# ESP32.net
KiCad netlist of a schematic drawn in Altium Designer
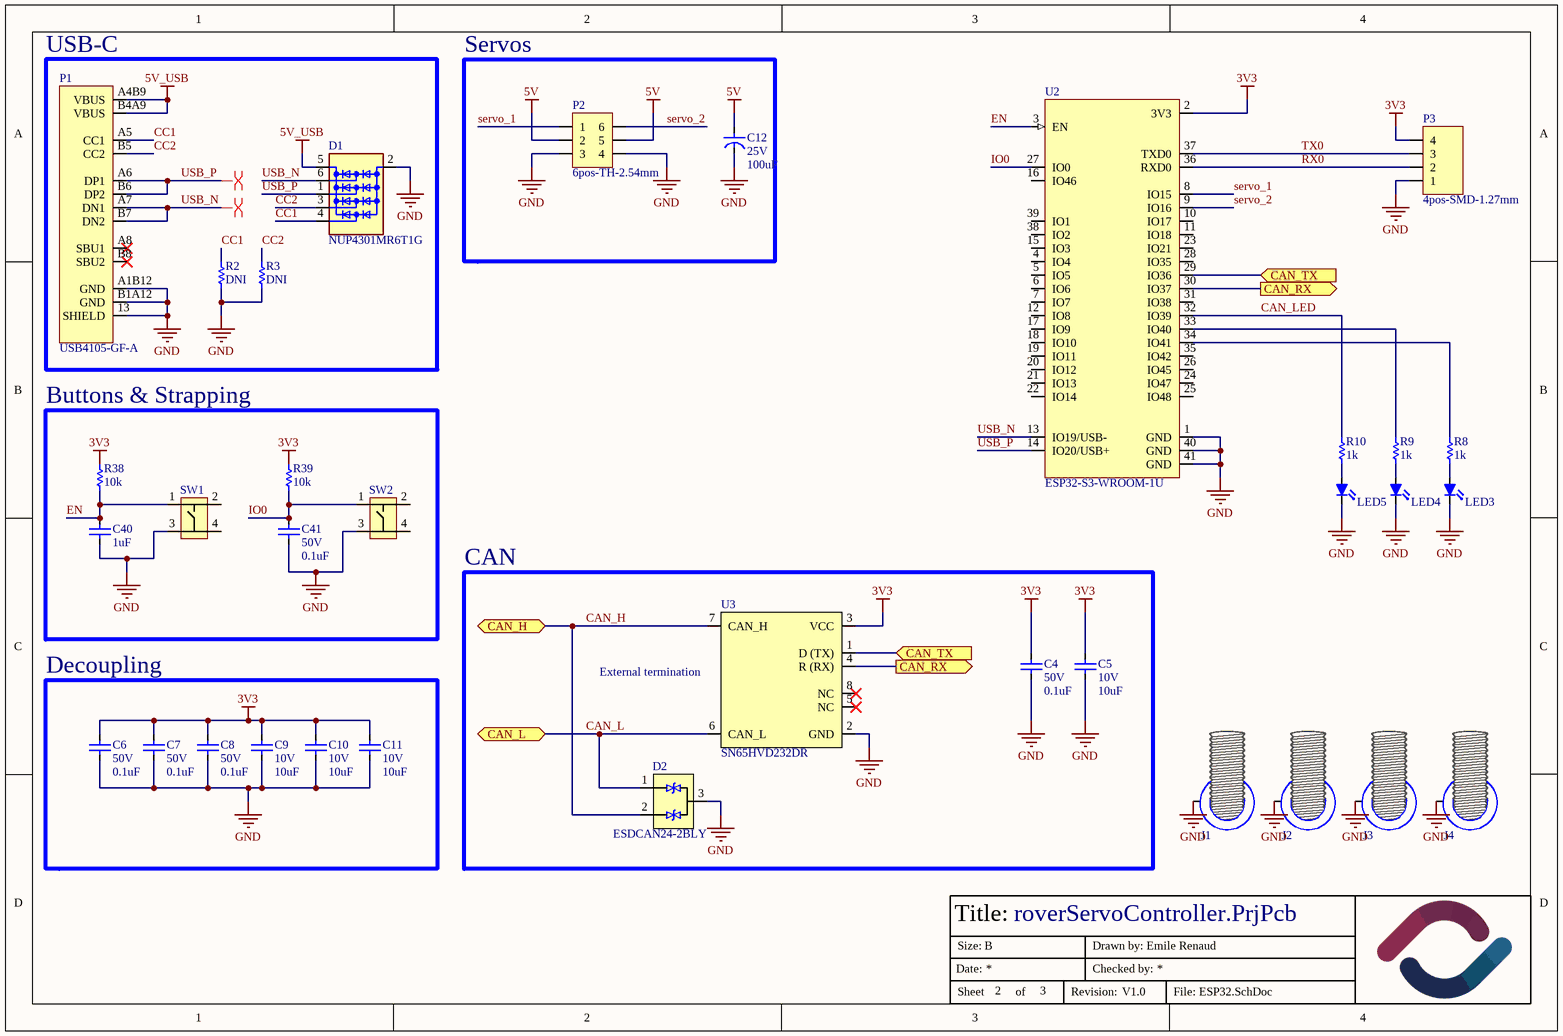
[diagram p0: ESP32.SchDoc]

(export (version "E")
  (design (tool "Eeschema 10.0.6"))
  (components
    (comp (ref "C4")
      (value "0.1uF")
      (footprint "CAPACITOR-0603")
      (description "Capacitor-0603-0.1uF-50V-X7R")
      (fields (field (name "VOLT") "50V"))
      (libsource (lib "Capacitors") (part "Capacitor-0603-0.1uF-50V-X7R"))
    )
    (comp (ref "C5")
      (value "10uF")
      (footprint "CAPACITOR-0603")
      (description "10 µF ±20% 10V Ceramic Capacitor X5R 0603 (1608 Metric)")
      (fields (field (name "VOLT") "10V") (field (name "Comment") "Capacitor-0603-10uF-10V-X5R"))
      (libsource (lib "Capacitors") (part "Capacitor-0603-10uF-10V-X5R"))
    )
    (comp (ref "C6")
      (value "0.1uF")
      (footprint "CAPACITOR-0603")
      (description "Capacitor-0603-0.1uF-50V-X7R")
      (fields (field (name "VOLT") "50V"))
      (libsource (lib "Capacitors") (part "Capacitor-0603-0.1uF-50V-X7R"))
    )
    (comp (ref "C7")
      (value "0.1uF")
      (footprint "CAPACITOR-0603")
      (description "Capacitor-0603-0.1uF-50V-X7R")
      (fields (field (name "VOLT") "50V"))
      (libsource (lib "Capacitors") (part "Capacitor-0603-0.1uF-50V-X7R"))
    )
    (comp (ref "C8")
      (value "0.1uF")
      (footprint "CAPACITOR-0603")
      (description "Capacitor-0603-0.1uF-50V-X7R")
      (fields (field (name "VOLT") "50V"))
      (libsource (lib "Capacitors") (part "Capacitor-0603-0.1uF-50V-X7R"))
    )
    (comp (ref "C9")
      (value "10uF")
      (footprint "CAPACITOR-0603")
      (description "10 µF ±20% 10V Ceramic Capacitor X5R 0603 (1608 Metric)")
      (fields (field (name "VOLT") "10V") (field (name "Comment") "Capacitor-0603-10uF-10V-X5R"))
      (libsource (lib "Capacitors") (part "Capacitor-0603-10uF-10V-X5R"))
    )
    (comp (ref "C10")
      (value "10uF")
      (footprint "CAPACITOR-0603")
      (description "10 µF ±20% 10V Ceramic Capacitor X5R 0603 (1608 Metric)")
      (fields (field (name "VOLT") "10V") (field (name "Comment") "Capacitor-0603-10uF-10V-X5R"))
      (libsource (lib "Capacitors") (part "Capacitor-0603-10uF-10V-X5R"))
    )
    (comp (ref "C11")
      (value "10uF")
      (footprint "CAPACITOR-0603")
      (description "10 µF ±20% 10V Ceramic Capacitor X5R 0603 (1608 Metric)")
      (fields (field (name "VOLT") "10V") (field (name "Comment") "Capacitor-0603-10uF-10V-X5R"))
      (libsource (lib "Capacitors") (part "Capacitor-0603-10uF-10V-X5R"))
    )
    (comp (ref "C12")
      (value "100uF")
      (footprint "CAPACITOR-Aluminium-5x11mm-2mmPitch - SIDE")
      (description "CAP ALUM 100UF 20% 25V RADIAL")
      (fields (field (name "VOLT") "25V") (field (name "Comment") "CAP ALUM 100UF 20% 25V RADIAL SIDE"))
      (libsource (lib "Capacitors-Electrolytic") (part "Capacitor-100uF-25V-Side"))
    )
    (comp (ref "C40")
      (value "1uF")
      (footprint "CAPACITOR-0603")
      (description "Capacitor-0603-1uF-25V-X5R")
      (libsource (lib "Capacitors") (part "Capacitor-0603-1uF-25V-X5R"))
    )
    (comp (ref "C41")
      (value "0.1uF")
      (footprint "CAPACITOR-0603")
      (description "Capacitor-0603-0.1uF-50V-X7R")
      (fields (field (name "VOLT") "50V"))
      (libsource (lib "Capacitors") (part "Capacitor-0603-0.1uF-50V-X7R"))
    )
    (comp (ref "D1")
      (value "NUP4301MR6T1G")
      (footprint "SOT-23-6")
      (description "4CH Clamp Ipp Tvs Diode Surface Mount SOT23-6 (SC74)")
      (libsource (lib "diodes") (part "NUP4301MR6T1G"))
    )
    (comp (ref "D2")
      (value "ESDCAN24-2BLY")
      (footprint "SOT-23-3")
      (description "55V Clamp 6A (8/20µs) Ipp Tvs Diode Surface Mount SOT-23")
      (libsource (lib "diodes-tvs") (part "ESDCAN24-2BLY"))
    )
    (comp (ref "J1")
      (value "hole")
      (footprint "HOLE-3.40MM-M3-8MMEYELET")
      (description "Hole for M3 Bolt with 8mm pad")
      (libsource (lib "JumpersAndHoles") (part "Hole 3.40mm M3-Eyelet"))
    )
    (comp (ref "J2")
      (value "hole")
      (footprint "HOLE-3.40MM-M3-8MMEYELET")
      (description "Hole for M3 Bolt with 8mm pad")
      (libsource (lib "JumpersAndHoles") (part "Hole 3.40mm M3-Eyelet"))
    )
    (comp (ref "J3")
      (value "hole")
      (footprint "HOLE-3.40MM-M3-8MMEYELET")
      (description "Hole for M3 Bolt with 8mm pad")
      (libsource (lib "JumpersAndHoles") (part "Hole 3.40mm M3-Eyelet"))
    )
    (comp (ref "J4")
      (value "hole")
      (footprint "HOLE-3.40MM-M3-8MMEYELET")
      (description "Hole for M3 Bolt with 8mm pad")
      (libsource (lib "JumpersAndHoles") (part "Hole 3.40mm M3-Eyelet"))
    )
    (comp (ref "LED3")
      (value "3147-B1931NB--20C007614U1930CT-ND")
      (footprint "LED-0603-2PIN-SILKSCREEN")
      (description "LED BLUE CLEAR 0603 SMD")
      (libsource (lib "LEDs") (part "LED_BLUE"))
    )
    (comp (ref "LED4")
      (value "3147-B1931NB--20C007614U1930CT-ND")
      (footprint "LED-0603-2PIN-SILKSCREEN")
      (description "LED BLUE CLEAR 0603 SMD")
      (libsource (lib "LEDs") (part "LED_BLUE"))
    )
    (comp (ref "LED5")
      (value "3147-B1931NB--20C007614U1930CT-ND")
      (footprint "LED-0603-2PIN-SILKSCREEN")
      (description "LED BLUE CLEAR 0603 SMD")
      (libsource (lib "LEDs") (part "LED_BLUE"))
    )
    (comp (ref "P1")
      (value "USB4105-GF-A")
      (footprint "USB-C")
      (description "CONN RCP USB2.0 TYP C 24P SMD RA\r\n5A")
      (libsource (lib "PC-connector") (part "USB4105-GF-A"))
    )
    (comp (ref "P2")
      (value "6pos-TH-2.54mm")
      (footprint "HDR2X3")
      (description "6pos TH 2.54mm Header")
      (libsource (lib "Header") (part "6pos-TH-2.54mm 2x3"))
    )
    (comp (ref "P3")
      (value "4pos-SMD-1.27mm")
      (footprint "HDR1X4-SMD-50mils")
      (description "4pos SMD 1.27mm")
      (libsource (lib "Header") (part "4pos-SMD-1.27mm"))
    )
    (comp (ref "R2")
      (value "DNI")
      (footprint "RESISTOR-0603")
      (description "0603 footprint DO NOT INSTALL")
      (fields (field (name "Comment") "Resistor-0603-5.1k"))
      (libsource (lib "Resistors") (part "Resistor-0603-DNI"))
    )
    (comp (ref "R3")
      (value "DNI")
      (footprint "RESISTOR-0603")
      (description "0603 footprint DO NOT INSTALL")
      (fields (field (name "Comment") "Resistor-0603-5.1k"))
      (libsource (lib "Resistors") (part "Resistor-0603-DNI"))
    )
    (comp (ref "R8")
      (value "1k")
      (footprint "Resistor-0603")
      (description "Resistor0603-1k")
      (fields (field (name "Comment") "SMT resistor"))
      (libsource (lib "Resistors") (part "Resistor-0603-1k"))
    )
    (comp (ref "R9")
      (value "1k")
      (footprint "Resistor-0603")
      (description "Resistor0603-1k")
      (fields (field (name "Comment") "SMT resistor"))
      (libsource (lib "Resistors") (part "Resistor-0603-1k"))
    )
    (comp (ref "R10")
      (value "1k")
      (footprint "Resistor-0603")
      (description "Resistor0603-1k")
      (fields (field (name "Comment") "SMT resistor"))
      (libsource (lib "Resistors") (part "Resistor-0603-1k"))
    )
    (comp (ref "R38")
      (value "10k")
      (footprint "Resistor-0603")
      (description "Resistor0603-10k")
      (fields (field (name "Comment") "SMT resistor"))
      (libsource (lib "Resistors") (part "Resistor0603-10k"))
    )
    (comp (ref "R39")
      (value "10k")
      (footprint "Resistor-0603")
      (description "Resistor0603-10k")
      (fields (field (name "Comment") "SMT resistor"))
      (libsource (lib "Resistors") (part "Resistor0603-10k"))
    )
    (comp (ref "SW1")
      (value "PTS815 SJM 250 SMTR LFS")
      (footprint "SW4_PTS815 SJM 250 SMTR LFS_CNK")
      (description "TACT 4.2 X 3.2, 2.5 MM H, 180GF,")
      (libsource (lib "THTPushButtonSwitches") (part "PTS815 SJM 250 SMTR LFS"))
    )
    (comp (ref "SW2")
      (value "PTS815 SJM 250 SMTR LFS")
      (footprint "SW4_PTS815 SJM 250 SMTR LFS_CNK")
      (description "TACT 4.2 X 3.2, 2.5 MM H, 180GF,")
      (libsource (lib "THTPushButtonSwitches") (part "PTS815 SJM 250 SMTR LFS"))
    )
    (comp (ref "U2")
      (value "ESP32-S3-WROOM-1U")
      (footprint "ESP32-S3-WROOM-1U")
      (description "2.4 GHz Wi-Fi (802.11 b/g/n) and Bluetooth 5 (LE) module")
      (fields (field (name "MF") "Espressif Systems"))
      (libsource (lib "Microcontrollers") (part "ESP32-S3-WROOM-1U"))
    )
    (comp (ref "U3")
      (value "SN65HVD232DR")
      (footprint "SOIC-8")
      (description "1/1 Transceiver Half CANbus 8-SOIC")
      (libsource (lib "Transceiver") (part "SN65HVD232DR"))
    )
  )
  (nets
    (net (code "1") (name "/CAN_H") (class "Default")
      (node (ref "D2") (pin "2") (pinfunction "GND_2") (pintype "passive"))
      (node (ref "U3") (pin "7") (pinfunction "CAN_H_7") (pintype "passive"))
    )
    (net (code "2") (name "/CAN_L") (class "Default")
      (node (ref "D2") (pin "1") (pinfunction "L2_1") (pintype "passive"))
      (node (ref "U3") (pin "6") (pinfunction "CAN_L_6") (pintype "passive"))
    )
    (net (code "3") (name "/CAN_LED") (class "Default")
      (node (ref "R10") (pin "2") (pinfunction "2_2") (pintype "passive"))
      (node (ref "U2") (pin "32") (pinfunction "IO39_32") (pintype "bidirectional"))
    )
    (net (code "4") (name "/CAN_RX") (class "Default")
      (node (ref "U2") (pin "30") (pinfunction "IO37_30") (pintype "bidirectional"))
      (node (ref "U3") (pin "4") (pinfunction "R_(RX)_4") (pintype "passive"))
    )
    (net (code "5") (name "/CAN_TX") (class "Default")
      (node (ref "U2") (pin "29") (pinfunction "IO36_29") (pintype "bidirectional"))
      (node (ref "U3") (pin "1") (pinfunction "D_(TX)_1") (pintype "passive"))
    )
    (net (code "6") (name "/CC1") (class "Default")
      (node (ref "D1") (pin "4") (pinfunction "L4_4") (pintype "passive"))
      (node (ref "P1") (pin "A5") (pinfunction "CC1_A5") (pintype "passive"))
      (node (ref "R2") (pin "2") (pinfunction "2_2") (pintype "passive"))
    )
    (net (code "7") (name "/CC2") (class "Default")
      (node (ref "D1") (pin "3") (pinfunction "L3_3") (pintype "passive"))
      (node (ref "P1") (pin "B5") (pinfunction "CC2_B5") (pintype "passive"))
      (node (ref "R3") (pin "2") (pinfunction "2_2") (pintype "passive"))
    )
    (net (code "8") (name "/EN") (class "Default")
      (node (ref "C40") (pin "2") (pinfunction "2_2") (pintype "passive"))
      (node (ref "R38") (pin "1") (pinfunction "1_1") (pintype "passive"))
      (node (ref "SW1") (pin "1") (pinfunction "1_1") (pintype "passive"))
      (node (ref "U2") (pin "3") (pinfunction "EN_3") (pintype "input"))
    )
    (net (code "9") (name "/IO0") (class "Default")
      (node (ref "C41") (pin "2") (pinfunction "2_2") (pintype "passive"))
      (node (ref "R39") (pin "1") (pinfunction "1_1") (pintype "passive"))
      (node (ref "SW2") (pin "1") (pinfunction "1_1") (pintype "passive"))
      (node (ref "U2") (pin "27") (pinfunction "IO0_27") (pintype "bidirectional"))
    )
    (net (code "10") (name "/RX0") (class "Default")
      (node (ref "P3") (pin "2") (pinfunction "2_2") (pintype "passive"))
      (node (ref "U2") (pin "36") (pinfunction "RXD0_36") (pintype "bidirectional"))
    )
    (net (code "11") (name "/TX0") (class "Default")
      (node (ref "P3") (pin "3") (pinfunction "3_3") (pintype "passive"))
      (node (ref "U2") (pin "37") (pinfunction "TXD0_37") (pintype "bidirectional"))
    )
    (net (code "12") (name "/USB_N") (class "Default")
      (node (ref "D1") (pin "6") (pinfunction "L1_6") (pintype "passive"))
      (node (ref "P1") (pin "A7") (pinfunction "DN1_A7") (pintype "passive"))
      (node (ref "P1") (pin "B7") (pinfunction "DN2_B7") (pintype "passive"))
      (node (ref "U2") (pin "13") (pinfunction "IO19/USB-_13") (pintype "bidirectional"))
    )
    (net (code "13") (name "/USB_P") (class "Default")
      (node (ref "D1") (pin "1") (pinfunction "L2_1") (pintype "passive"))
      (node (ref "P1") (pin "A6") (pinfunction "DP1_A6") (pintype "passive"))
      (node (ref "P1") (pin "B6") (pinfunction "DP2_B6") (pintype "passive"))
      (node (ref "U2") (pin "14") (pinfunction "IO20/USB+_14") (pintype "bidirectional"))
    )
    (net (code "14") (name "/servo_1") (class "Default")
      (node (ref "P2") (pin "1") (pinfunction "1_1") (pintype "passive"))
      (node (ref "U2") (pin "8") (pinfunction "IO15_8") (pintype "bidirectional"))
    )
    (net (code "15") (name "/servo_2") (class "Default")
      (node (ref "P2") (pin "6") (pinfunction "6_6") (pintype "passive"))
      (node (ref "U2") (pin "9") (pinfunction "IO16_9") (pintype "bidirectional"))
    )
    (net (code "16") (name "3V3") (class "Default")
      (node (ref "C10") (pin "2") (pinfunction "2_2") (pintype "passive"))
      (node (ref "C11") (pin "2") (pinfunction "2_2") (pintype "passive"))
      (node (ref "C4") (pin "2") (pinfunction "2_2") (pintype "passive"))
      (node (ref "C5") (pin "2") (pinfunction "2_2") (pintype "passive"))
      (node (ref "C6") (pin "2") (pinfunction "2_2") (pintype "passive"))
      (node (ref "C7") (pin "2") (pinfunction "2_2") (pintype "passive"))
      (node (ref "C8") (pin "2") (pinfunction "2_2") (pintype "passive"))
      (node (ref "C9") (pin "2") (pinfunction "2_2") (pintype "passive"))
      (node (ref "P3") (pin "4") (pinfunction "4_4") (pintype "passive"))
      (node (ref "R38") (pin "2") (pinfunction "2_2") (pintype "passive"))
      (node (ref "R39") (pin "2") (pinfunction "2_2") (pintype "passive"))
      (node (ref "U2") (pin "2") (pinfunction "3V3_2") (pintype "power_in"))
      (node (ref "U3") (pin "3") (pinfunction "VCC_3") (pintype "passive"))
    )
    (net (code "17") (name "5V") (class "Default")
      (node (ref "C12") (pin "1") (pinfunction "1_1") (pintype "passive"))
      (node (ref "P2") (pin "2") (pinfunction "2_2") (pintype "passive"))
      (node (ref "P2") (pin "5") (pinfunction "5_5") (pintype "passive"))
    )
    (net (code "18") (name "5V_USB") (class "Default")
      (node (ref "D1") (pin "5") (pinfunction "VDD_5") (pintype "passive"))
      (node (ref "P1") (pin "A4B9") (pinfunction "VBUS_A4B9") (pintype "passive"))
      (node (ref "P1") (pin "B4A9") (pinfunction "VBUS_B4A9") (pintype "passive"))
    )
    (net (code "19") (name "GND") (class "Default")
      (node (ref "C10") (pin "1") (pinfunction "1_1") (pintype "passive"))
      (node (ref "C11") (pin "1") (pinfunction "1_1") (pintype "passive"))
      (node (ref "C12") (pin "2") (pinfunction "2_2") (pintype "passive"))
      (node (ref "C4") (pin "1") (pinfunction "1_1") (pintype "passive"))
      (node (ref "C40") (pin "1") (pinfunction "1_1") (pintype "passive"))
      (node (ref "C41") (pin "1") (pinfunction "1_1") (pintype "passive"))
      (node (ref "C5") (pin "1") (pinfunction "1_1") (pintype "passive"))
      (node (ref "C6") (pin "1") (pinfunction "1_1") (pintype "passive"))
      (node (ref "C7") (pin "1") (pinfunction "1_1") (pintype "passive"))
      (node (ref "C8") (pin "1") (pinfunction "1_1") (pintype "passive"))
      (node (ref "C9") (pin "1") (pinfunction "1_1") (pintype "passive"))
      (node (ref "D1") (pin "2") (pinfunction "GND_2") (pintype "passive"))
      (node (ref "D2") (pin "3") (pinfunction "L3_3") (pintype "passive"))
      (node (ref "J1") (pin "1") (pinfunction "1_1") (pintype "passive"))
      (node (ref "J2") (pin "1") (pinfunction "1_1") (pintype "passive"))
      (node (ref "J3") (pin "1") (pinfunction "1_1") (pintype "passive"))
      (node (ref "J4") (pin "1") (pinfunction "1_1") (pintype "passive"))
      (node (ref "LED3") (pin "1") (pinfunction "K_1") (pintype "passive"))
      (node (ref "LED4") (pin "1") (pinfunction "K_1") (pintype "passive"))
      (node (ref "LED5") (pin "1") (pinfunction "K_1") (pintype "passive"))
      (node (ref "P1") (pin "13") (pinfunction "SHIELD_13") (pintype "passive"))
      (node (ref "P1") (pin "A1B12") (pinfunction "GND_A1B12") (pintype "passive"))
      (node (ref "P1") (pin "B1A12") (pinfunction "GND_B1A12") (pintype "passive"))
      (node (ref "P2") (pin "3") (pinfunction "3_3") (pintype "passive"))
      (node (ref "P2") (pin "4") (pinfunction "4_4") (pintype "passive"))
      (node (ref "P3") (pin "1") (pinfunction "1_1") (pintype "passive"))
      (node (ref "R2") (pin "1") (pinfunction "1_1") (pintype "passive"))
      (node (ref "R3") (pin "1") (pinfunction "1_1") (pintype "passive"))
      (node (ref "SW1") (pin "3") (pinfunction "3_3") (pintype "passive"))
      (node (ref "SW2") (pin "3") (pinfunction "3_3") (pintype "passive"))
      (node (ref "U2") (pin "1") (pinfunction "GND_1") (pintype "power_in"))
      (node (ref "U2") (pin "40") (pinfunction "GND_40") (pintype "power_in"))
      (node (ref "U2") (pin "41") (pinfunction "GND_41") (pintype "power_in"))
      (node (ref "U3") (pin "2") (pinfunction "GND_2") (pintype "passive"))
    )
    (net (code "20") (name "Net-(LED3-R)") (class "Default")
      (node (ref "LED3") (pin "2") (pinfunction "R_2") (pintype "passive"))
      (node (ref "R8") (pin "1") (pinfunction "1_1") (pintype "passive"))
    )
    (net (code "21") (name "Net-(LED4-R)") (class "Default")
      (node (ref "LED4") (pin "2") (pinfunction "R_2") (pintype "passive"))
      (node (ref "R9") (pin "1") (pinfunction "1_1") (pintype "passive"))
    )
    (net (code "22") (name "Net-(LED5-R)") (class "Default")
      (node (ref "LED5") (pin "2") (pinfunction "R_2") (pintype "passive"))
      (node (ref "R10") (pin "1") (pinfunction "1_1") (pintype "passive"))
    )
    (net (code "23") (name "Net-(U2-IO40)") (class "Default")
      (node (ref "R9") (pin "2") (pinfunction "2_2") (pintype "passive"))
      (node (ref "U2") (pin "33") (pinfunction "IO40_33") (pintype "bidirectional"))
    )
    (net (code "24") (name "Net-(U2-IO41)") (class "Default")
      (node (ref "R8") (pin "2") (pinfunction "2_2") (pintype "passive"))
      (node (ref "U2") (pin "34") (pinfunction "IO41_34") (pintype "bidirectional"))
    )
    (net (code "25") (name "unconnected-(P1-SBU1-PadA8)") (class "Default")
      (node (ref "P1") (pin "A8") (pinfunction "SBU1_A8") (pintype "passive+no_connect"))
    )
    (net (code "26") (name "unconnected-(P1-SBU2-PadB8)") (class "Default")
      (node (ref "P1") (pin "B8") (pinfunction "SBU2_B8") (pintype "passive+no_connect"))
    )
    (net (code "27") (name "unconnected-(SW1-Pad2)") (class "Default")
      (node (ref "SW1") (pin "2") (pinfunction "2_2") (pintype "passive"))
    )
    (net (code "28") (name "unconnected-(SW1-Pad4)") (class "Default")
      (node (ref "SW1") (pin "4") (pinfunction "4_4") (pintype "passive"))
    )
    (net (code "29") (name "unconnected-(SW2-Pad2)") (class "Default")
      (node (ref "SW2") (pin "2") (pinfunction "2_2") (pintype "passive"))
    )
    (net (code "30") (name "unconnected-(SW2-Pad4)") (class "Default")
      (node (ref "SW2") (pin "4") (pinfunction "4_4") (pintype "passive"))
    )
    (net (code "31") (name "unconnected-(U2-IO1-Pad39)") (class "Default")
      (node (ref "U2") (pin "39") (pinfunction "IO1_39") (pintype "bidirectional"))
    )
    (net (code "32") (name "unconnected-(U2-IO2-Pad38)") (class "Default")
      (node (ref "U2") (pin "38") (pinfunction "IO2_38") (pintype "bidirectional"))
    )
    (net (code "33") (name "unconnected-(U2-IO3-Pad15)") (class "Default")
      (node (ref "U2") (pin "15") (pinfunction "IO3_15") (pintype "bidirectional"))
    )
    (net (code "34") (name "unconnected-(U2-IO4-Pad4)") (class "Default")
      (node (ref "U2") (pin "4") (pinfunction "IO4_4") (pintype "bidirectional"))
    )
    (net (code "35") (name "unconnected-(U2-IO5-Pad5)") (class "Default")
      (node (ref "U2") (pin "5") (pinfunction "IO5_5") (pintype "bidirectional"))
    )
    (net (code "36") (name "unconnected-(U2-IO6-Pad6)") (class "Default")
      (node (ref "U2") (pin "6") (pinfunction "IO6_6") (pintype "bidirectional"))
    )
    (net (code "37") (name "unconnected-(U2-IO7-Pad7)") (class "Default")
      (node (ref "U2") (pin "7") (pinfunction "IO7_7") (pintype "bidirectional"))
    )
    (net (code "38") (name "unconnected-(U2-IO8-Pad12)") (class "Default")
      (node (ref "U2") (pin "12") (pinfunction "IO8_12") (pintype "bidirectional"))
    )
    (net (code "39") (name "unconnected-(U2-IO9-Pad17)") (class "Default")
      (node (ref "U2") (pin "17") (pinfunction "IO9_17") (pintype "bidirectional"))
    )
    (net (code "40") (name "unconnected-(U2-IO10-Pad18)") (class "Default")
      (node (ref "U2") (pin "18") (pinfunction "IO10_18") (pintype "bidirectional"))
    )
    (net (code "41") (name "unconnected-(U2-IO11-Pad19)") (class "Default")
      (node (ref "U2") (pin "19") (pinfunction "IO11_19") (pintype "bidirectional"))
    )
    (net (code "42") (name "unconnected-(U2-IO12-Pad20)") (class "Default")
      (node (ref "U2") (pin "20") (pinfunction "IO12_20") (pintype "bidirectional"))
    )
    (net (code "43") (name "unconnected-(U2-IO13-Pad21)") (class "Default")
      (node (ref "U2") (pin "21") (pinfunction "IO13_21") (pintype "bidirectional"))
    )
    (net (code "44") (name "unconnected-(U2-IO14-Pad22)") (class "Default")
      (node (ref "U2") (pin "22") (pinfunction "IO14_22") (pintype "bidirectional"))
    )
    (net (code "45") (name "unconnected-(U2-IO17-Pad10)") (class "Default")
      (node (ref "U2") (pin "10") (pinfunction "IO17_10") (pintype "bidirectional"))
    )
    (net (code "46") (name "unconnected-(U2-IO18-Pad11)") (class "Default")
      (node (ref "U2") (pin "11") (pinfunction "IO18_11") (pintype "bidirectional"))
    )
    (net (code "47") (name "unconnected-(U2-IO21-Pad23)") (class "Default")
      (node (ref "U2") (pin "23") (pinfunction "IO21_23") (pintype "bidirectional"))
    )
    (net (code "48") (name "unconnected-(U2-IO35-Pad28)") (class "Default")
      (node (ref "U2") (pin "28") (pinfunction "IO35_28") (pintype "bidirectional"))
    )
    (net (code "49") (name "unconnected-(U2-IO38-Pad31)") (class "Default")
      (node (ref "U2") (pin "31") (pinfunction "IO38_31") (pintype "bidirectional"))
    )
    (net (code "50") (name "unconnected-(U2-IO42-Pad35)") (class "Default")
      (node (ref "U2") (pin "35") (pinfunction "IO42_35") (pintype "bidirectional"))
    )
    (net (code "51") (name "unconnected-(U2-IO45-Pad26)") (class "Default")
      (node (ref "U2") (pin "26") (pinfunction "IO45_26") (pintype "bidirectional"))
    )
    (net (code "52") (name "unconnected-(U2-IO46-Pad16)") (class "Default")
      (node (ref "U2") (pin "16") (pinfunction "IO46_16") (pintype "bidirectional"))
    )
    (net (code "53") (name "unconnected-(U2-IO47-Pad24)") (class "Default")
      (node (ref "U2") (pin "24") (pinfunction "IO47_24") (pintype "bidirectional"))
    )
    (net (code "54") (name "unconnected-(U2-IO48-Pad25)") (class "Default")
      (node (ref "U2") (pin "25") (pinfunction "IO48_25") (pintype "bidirectional"))
    )
    (net (code "55") (name "unconnected-(U3-NC-Pad5)") (class "Default")
      (node (ref "U3") (pin "5") (pinfunction "NC_5") (pintype "passive+no_connect"))
    )
    (net (code "56") (name "unconnected-(U3-NC-Pad8)") (class "Default")
      (node (ref "U3") (pin "8") (pinfunction "NC_8") (pintype "passive+no_connect"))
    )
  )
)
